# pickup3.net
KiCad netlist of a schematic drawn in EasyEDA
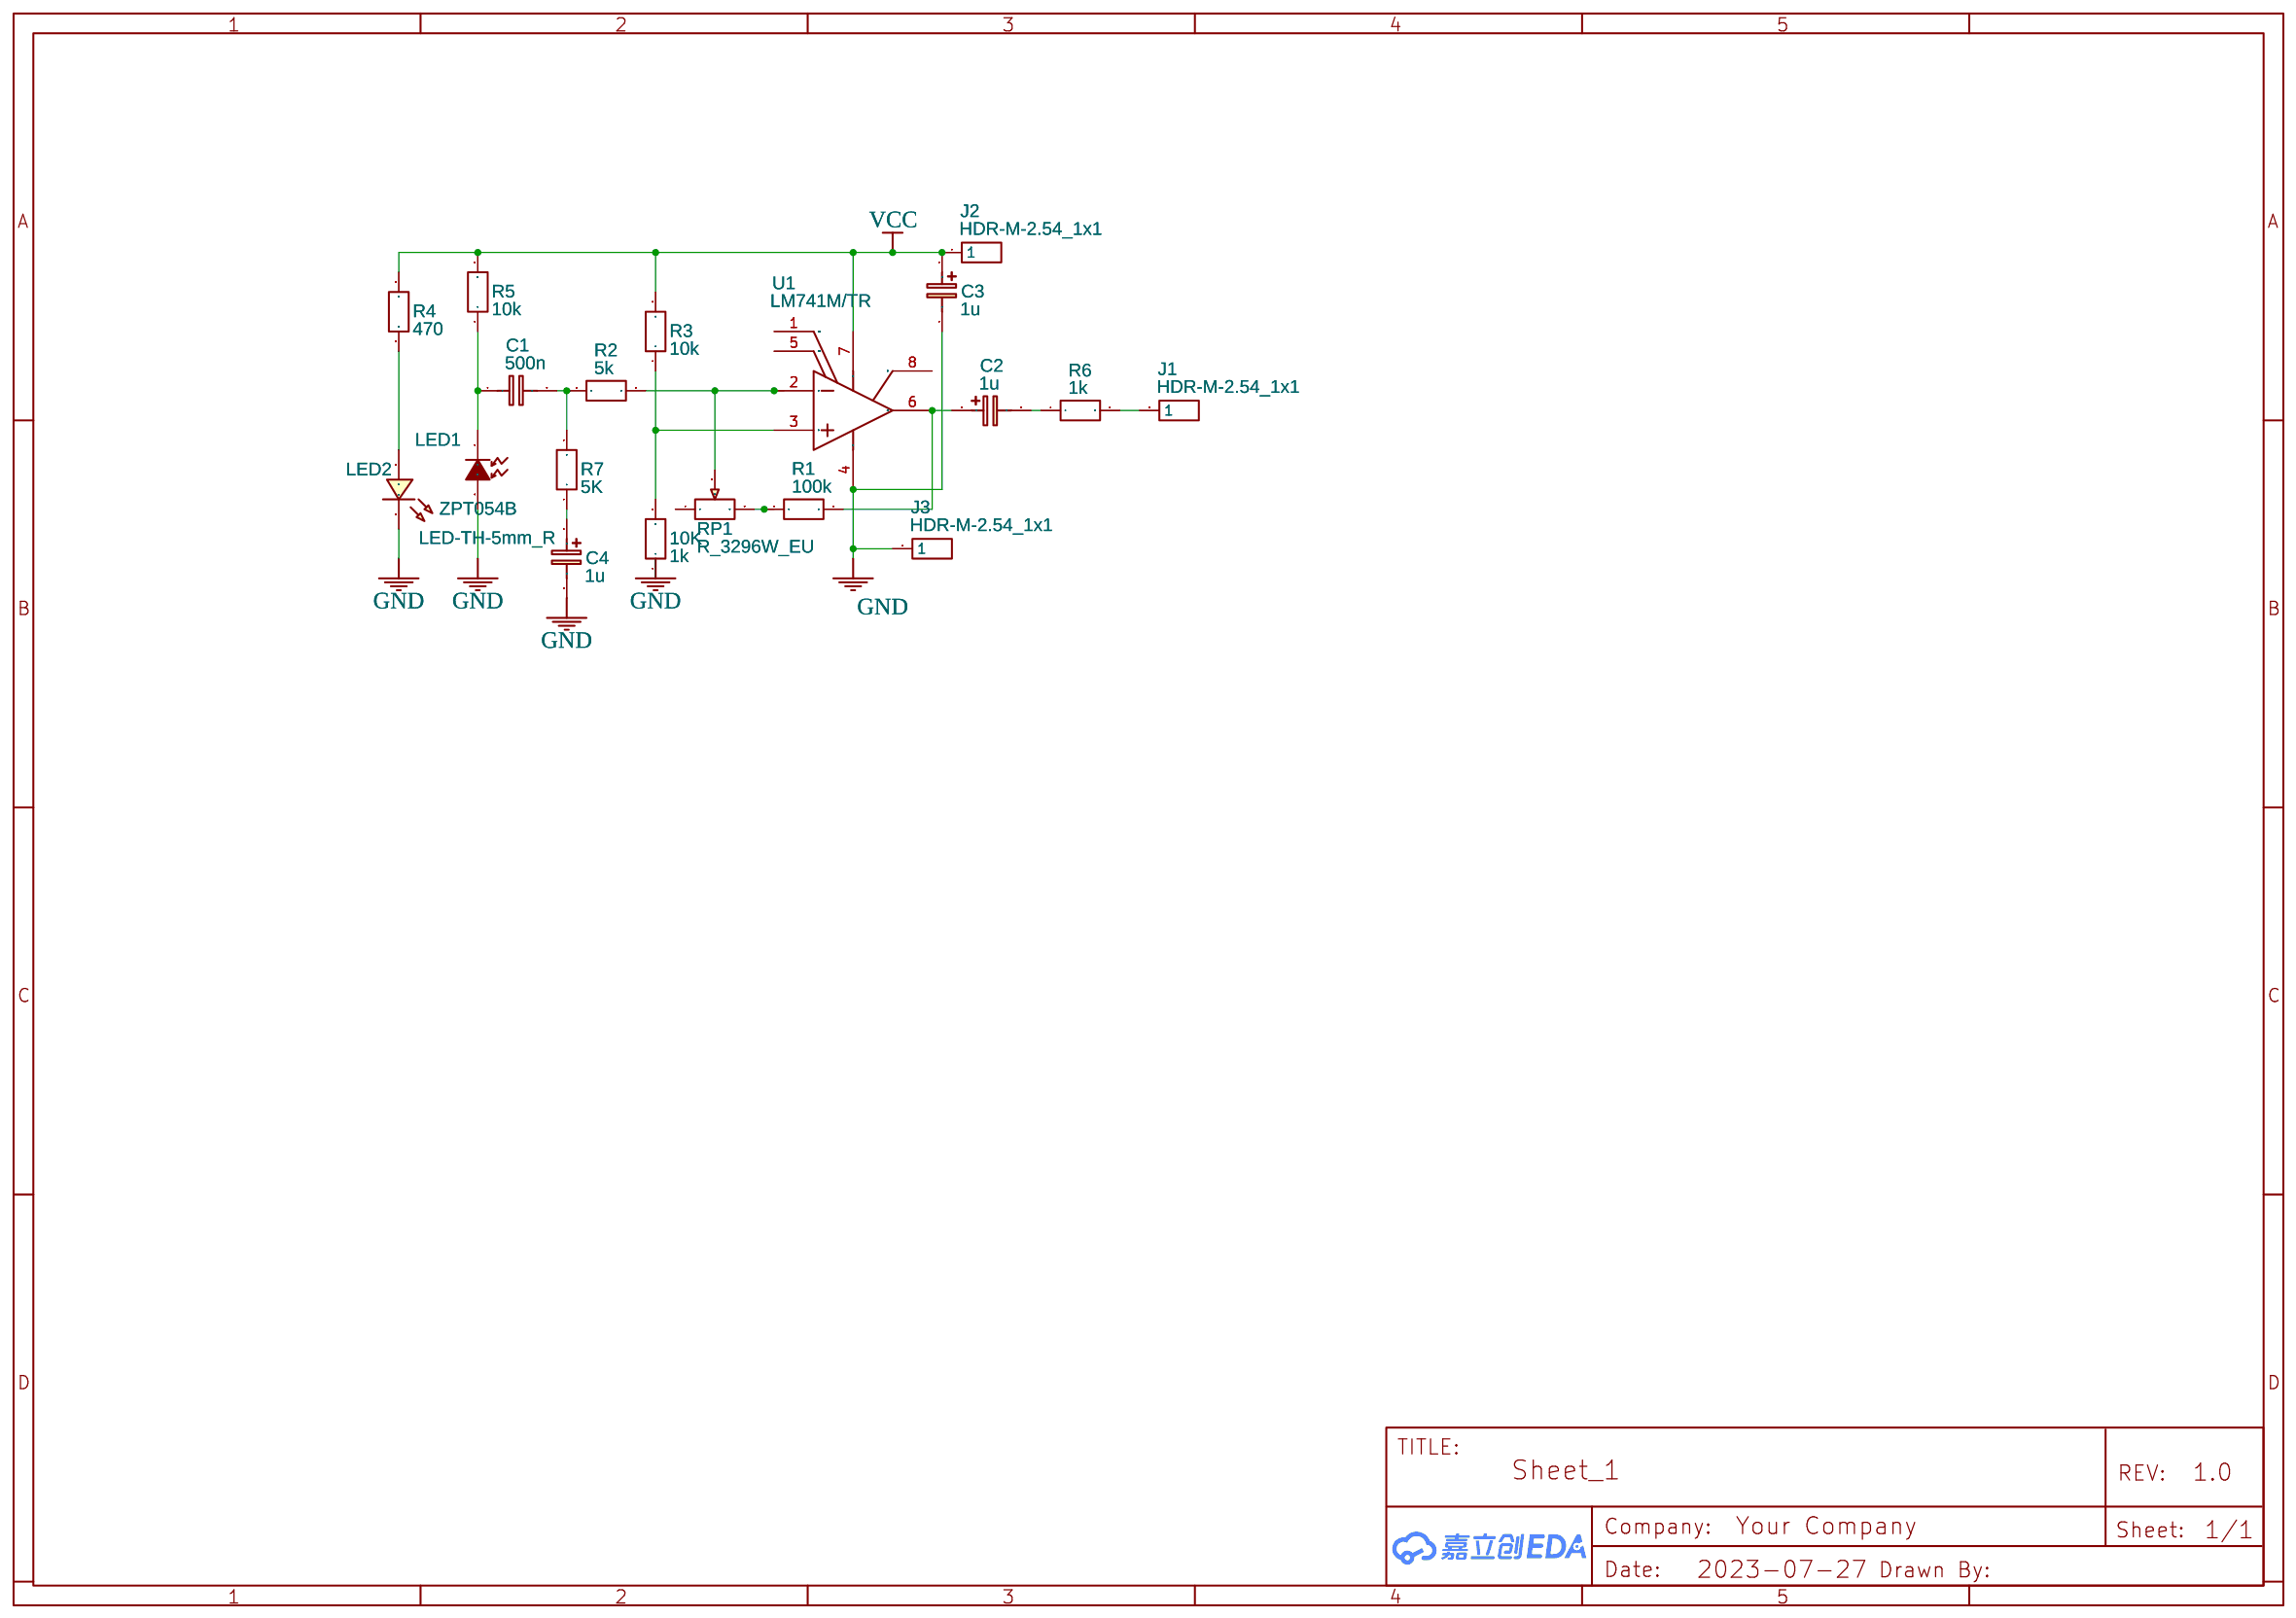
[diagram p0: schematic sheet]

(export (version "E")
  (design (tool "Eeschema 10.0.6"))
  (components
    (comp (ref "10K") (value "1k") (libsource (lib "") (part "R_0603_EU_2")))
    (comp (ref "C1") (value "500n") (libsource (lib "") (part "C_0603_EU")))
    (comp (ref "C2") (value "1u") (libsource (lib "") (part "C_Tan_SMD_A_EU")))
    (comp (ref "C3") (value "1u") (libsource (lib "") (part "C_Tan_SMD_A_EU_1")))
    (comp (ref "C4") (value "1u") (libsource (lib "") (part "C_Tan_SMD_A_EU_1")))
    (comp (ref "J1")
      (value "HDR-M-2.54_1x1")
      (fields (field (name "BOM_Supplier Part") "C81276"))
      (libsource (lib "") (part "HDR-M-2.54_1x1"))
    )
    (comp (ref "J2")
      (value "HDR-M-2.54_1x1")
      (fields (field (name "BOM_Supplier Part") "C81276"))
      (libsource (lib "") (part "HDR-M-2.54_1x1"))
    )
    (comp (ref "J3")
      (value "HDR-M-2.54_1x1")
      (fields (field (name "BOM_Supplier Part") "C81276"))
      (libsource (lib "") (part "HDR-M-2.54_1x1"))
    )
    (comp (ref "LED1")
      (value "ZPT054B")
      (fields (field (name "Manufacturer") "Chau Light"))
      (libsource (lib "") (part "ZPT054B"))
    )
    (comp (ref "LED2")
      (value "LED-TH-5mm_R")
      (fields
        (field (name "BOM_Manufacturer Part") "333-2SURD/S530-A3")
        (field (name "BOM_Supplier Part") "C87271")
      )
      (libsource (lib "") (part "LED-TH-5mm_R"))
    )
    (comp (ref "R1") (value "100k") (libsource (lib "") (part "R_0603_EU_1")))
    (comp (ref "R2") (value "5k") (libsource (lib "") (part "R_0603_EU_1")))
    (comp (ref "R3") (value "10k") (libsource (lib "") (part "R_0603_EU")))
    (comp (ref "R4") (value "470") (libsource (lib "") (part "R_0603_EU")))
    (comp (ref "R5") (value "10k") (libsource (lib "") (part "R_0603_EU")))
    (comp (ref "R6") (value "1k") (libsource (lib "") (part "R_0603_EU_1")))
    (comp (ref "R7") (value "5K") (libsource (lib "") (part "R_0603_EU")))
    (comp (ref "RP1") (value "R_3296W_EU") (libsource (lib "") (part "R_3296W_EU")))
    (comp (ref "U1")
      (value "LM741M/TR")
      (fields (field (name "Manufacturer") "HGSEMI(华冠)"))
      (libsource (lib "") (part "LM741M/TR"))
    )
  )
  (nets
    (net (code "1") (name "GND") (class "Default")
      (node (ref "10K") (pin "1") (pinfunction "1_1") (pintype "unspecified"))
      (node (ref "C3") (pin "2") (pinfunction "2_2") (pintype "unspecified"))
      (node (ref "C4") (pin "2") (pinfunction "2_2") (pintype "unspecified"))
      (node (ref "J3") (pin "1") (pinfunction "1_1") (pintype "input"))
      (node (ref "LED1") (pin "2") (pinfunction "C_2") (pintype "input"))
      (node (ref "LED2") (pin "2") (pinfunction "2_2") (pintype "unspecified"))
      (node (ref "U1") (pin "4") (pinfunction "V-_4") (pintype "passive"))
    )
    (net (code "2") (name "Net-(C1-Pad2)") (class "Default")
      (node (ref "C1") (pin "2") (pinfunction "2_2") (pintype "unspecified"))
      (node (ref "R2") (pin "1") (pinfunction "1_1") (pintype "unspecified"))
      (node (ref "R7") (pin "2") (pinfunction "2_2") (pintype "unspecified"))
    )
    (net (code "3") (name "Net-(C2-Pad2)") (class "Default")
      (node (ref "C2") (pin "2") (pinfunction "2_2") (pintype "unspecified"))
      (node (ref "R6") (pin "1") (pinfunction "1_1") (pintype "unspecified"))
    )
    (net (code "4") (name "Net-(C4-Pad1)") (class "Default")
      (node (ref "C4") (pin "1") (pinfunction "1_1") (pintype "unspecified"))
      (node (ref "R7") (pin "1") (pinfunction "1_1") (pintype "unspecified"))
    )
    (net (code "5") (name "Net-(J1-Pad1)") (class "Default")
      (node (ref "J1") (pin "1") (pinfunction "1_1") (pintype "input"))
      (node (ref "R6") (pin "2") (pinfunction "2_2") (pintype "unspecified"))
    )
    (net (code "6") (name "Net-(LED1-E)") (class "Default")
      (node (ref "C1") (pin "1") (pinfunction "1_1") (pintype "unspecified"))
      (node (ref "LED1") (pin "1") (pinfunction "E_1") (pintype "input"))
      (node (ref "R5") (pin "1") (pinfunction "1_1") (pintype "unspecified"))
    )
    (net (code "7") (name "Net-(LED2-Pad1)") (class "Default")
      (node (ref "LED2") (pin "1") (pinfunction "1_1") (pintype "unspecified"))
      (node (ref "R4") (pin "1") (pinfunction "1_1") (pintype "unspecified"))
    )
    (net (code "8") (name "Net-(R1-Pad1)") (class "Default")
      (node (ref "R1") (pin "1") (pinfunction "1_1") (pintype "unspecified"))
      (node (ref "RP1") (pin "3") (pinfunction "3_3") (pintype "input"))
    )
    (net (code "9") (name "Net-(U1-IN+)") (class "Default")
      (node (ref "10K") (pin "2") (pinfunction "2_2") (pintype "unspecified"))
      (node (ref "R3") (pin "1") (pinfunction "1_1") (pintype "unspecified"))
      (node (ref "U1") (pin "3") (pinfunction "IN+_3") (pintype "unspecified"))
    )
    (net (code "10") (name "Net-(U1-IN-)") (class "Default")
      (node (ref "R2") (pin "2") (pinfunction "2_2") (pintype "unspecified"))
      (node (ref "RP1") (pin "2") (pinfunction "2_2") (pintype "input"))
      (node (ref "U1") (pin "2") (pinfunction "IN-_2") (pintype "unspecified"))
    )
    (net (code "11") (name "Net-(U1-OUT)") (class "Default")
      (node (ref "C2") (pin "1") (pinfunction "1_1") (pintype "unspecified"))
      (node (ref "R1") (pin "2") (pinfunction "2_2") (pintype "unspecified"))
      (node (ref "U1") (pin "6") (pinfunction "OUT_6") (pintype "output"))
    )
    (net (code "12") (name "VCC") (class "Default")
      (node (ref "C3") (pin "1") (pinfunction "1_1") (pintype "unspecified"))
      (node (ref "J2") (pin "1") (pinfunction "1_1") (pintype "input"))
      (node (ref "R3") (pin "2") (pinfunction "2_2") (pintype "unspecified"))
      (node (ref "R4") (pin "2") (pinfunction "2_2") (pintype "unspecified"))
      (node (ref "R5") (pin "2") (pinfunction "2_2") (pintype "unspecified"))
      (node (ref "U1") (pin "7") (pinfunction "V+_7") (pintype "passive"))
    )
    (net (code "13") (name "unconnected-(RP1-Pad1)") (class "Default")
      (node (ref "RP1") (pin "1") (pinfunction "1_1") (pintype "input"))
    )
    (net (code "14") (name "unconnected-(U1-NC-Pad8)") (class "Default")
      (node (ref "U1") (pin "8") (pinfunction "NC_8") (pintype "unspecified"))
    )
    (net (code "15") (name "unconnected-(U1-OFFSET_NULL-Pad1)") (class "Default")
      (node (ref "U1") (pin "1") (pinfunction "OFFSET_NULL_1") (pintype "unspecified"))
    )
    (net (code "16") (name "unconnected-(U1-OFFSET_NULL-Pad5)") (class "Default")
      (node (ref "U1") (pin "5") (pinfunction "OFFSET_NULL_5") (pintype "unspecified"))
    )
  )
)
